# POV_V2.net
KiCad netlist of a schematic drawn in EAGLE
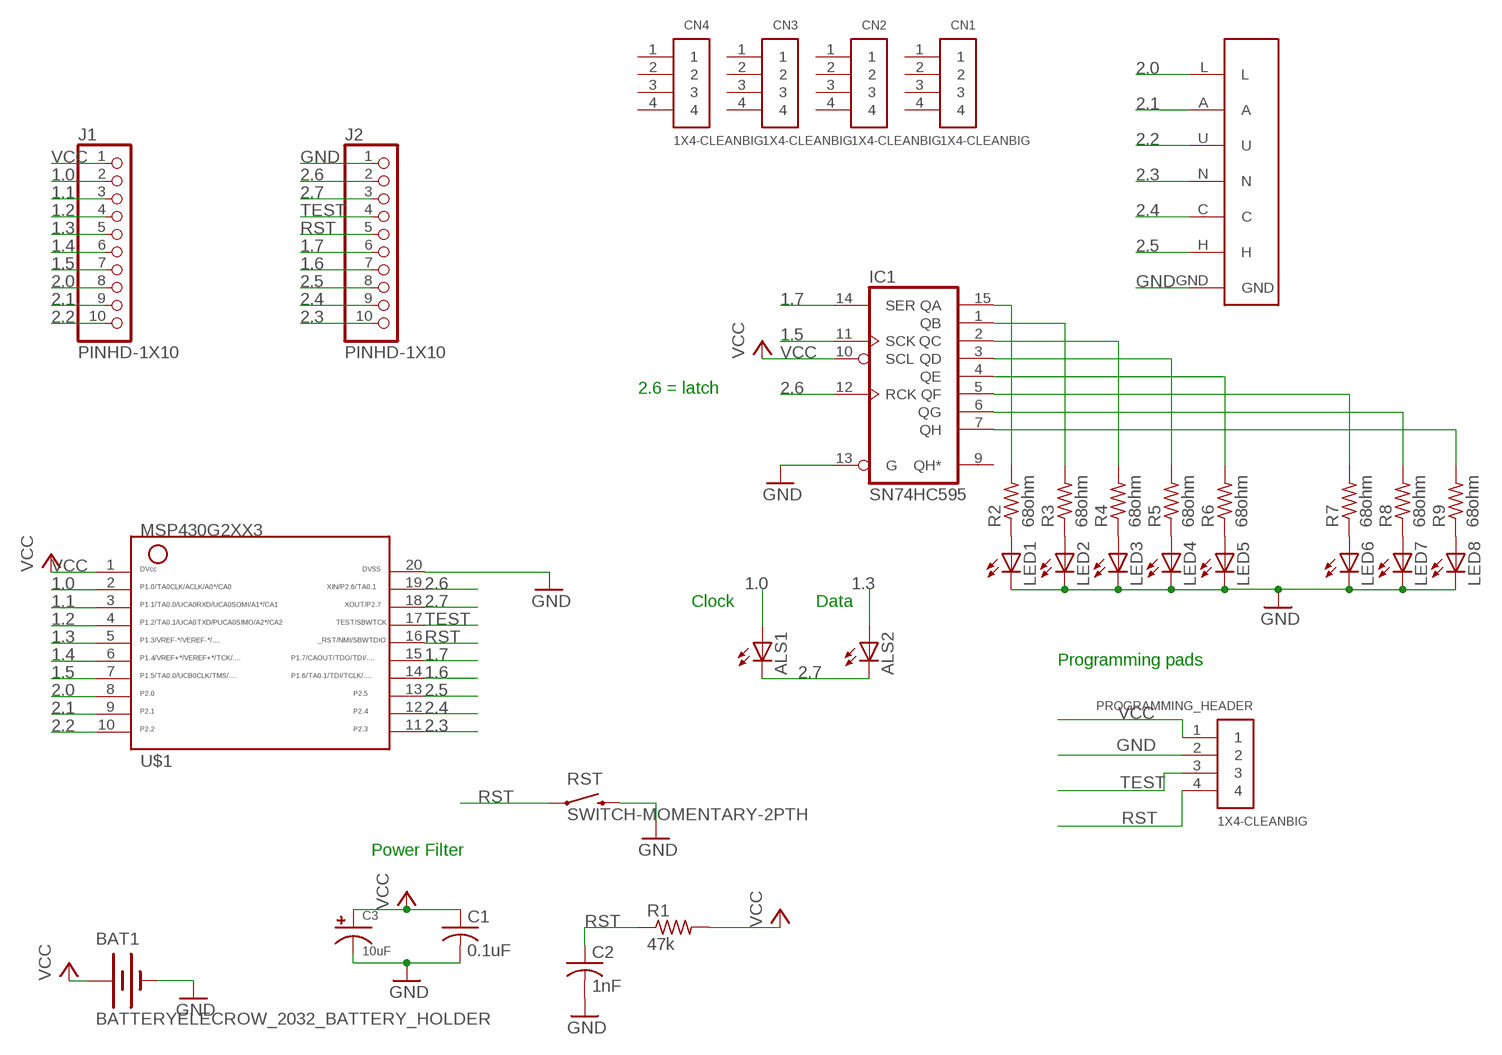
[diagram p0: schematic, sheet 1]

(export (version "E")
  (design (tool "Eeschema 10.0.6"))
  (components
    (comp (ref "ALS1")
      (value "LED3MM")
      (footprint "eagle-import:LED3MM")
      (libsource (lib "eagle-import") (part "LED3MM"))
    )
    (comp (ref "ALS2")
      (value "LED3MM")
      (footprint "eagle-import:LED3MM")
      (libsource (lib "eagle-import") (part "LED3MM"))
    )
    (comp (ref "BAT1")
      (value "BATTERYELECROW_2032_BATTERY_HOLDER")
      (footprint "eagle-import:BATTCON_20MM_4LEGS")
      (libsource (lib "eagle-import") (part "BATTERYELECROW_2032_BATTERY_HOLDER"))
    )
    (comp (ref "C1")
      (value "0.1uF")
      (footprint "eagle-import:C025-024X044")
      (libsource (lib "eagle-import") (part "C-US025-024X044"))
    )
    (comp (ref "C2")
      (value "1nF")
      (footprint "eagle-import:C025-024X044")
      (libsource (lib "eagle-import") (part "C-US025-024X044"))
    )
    (comp (ref "C3")
      (value "10uF")
      (footprint "eagle-import:E2,5-5")
      (libsource (lib "eagle-import") (part "CPOL-US"))
    )
    (comp (ref "CN1")
      (value "1X4-CLEANBIG")
      (footprint "eagle-import:1X04-CLEANBIG")
      (libsource (lib "eagle-import") (part "adafruit_1X4-CLEANBIG"))
    )
    (comp (ref "CN2")
      (value "1X4-CLEANBIG")
      (footprint "eagle-import:1X04-CLEANBIG")
      (libsource (lib "eagle-import") (part "adafruit_1X4-CLEANBIG"))
    )
    (comp (ref "CN3")
      (value "1X4-CLEANBIG")
      (footprint "eagle-import:1X04-CLEANBIG")
      (libsource (lib "eagle-import") (part "adafruit_1X4-CLEANBIG"))
    )
    (comp (ref "CN4")
      (value "1X4-CLEANBIG")
      (footprint "eagle-import:1X04-CLEANBIG")
      (libsource (lib "eagle-import") (part "adafruit_1X4-CLEANBIG"))
    )
    (comp (ref "IC1")
      (value "SN74HC595")
      (footprint "eagle-import:DIL16")
      (libsource (lib "eagle-import") (part "74595NLS"))
    )
    (comp (ref "J1")
      (value "PINHD-1X10")
      (footprint "eagle-import:1X10-BIG")
      (libsource (lib "eagle-import") (part "PINHD-1X10"))
    )
    (comp (ref "J2")
      (value "PINHD-1X10")
      (footprint "eagle-import:1X10-BIG")
      (libsource (lib "eagle-import") (part "PINHD-1X10"))
    )
    (comp (ref "LED1")
      (value "LED3MM")
      (footprint "eagle-import:LED3MM")
      (libsource (lib "eagle-import") (part "LED3MM"))
    )
    (comp (ref "LED2")
      (value "LED3MM")
      (footprint "eagle-import:LED3MM")
      (libsource (lib "eagle-import") (part "LED3MM"))
    )
    (comp (ref "LED3")
      (value "LED3MM")
      (footprint "eagle-import:LED3MM")
      (libsource (lib "eagle-import") (part "LED3MM"))
    )
    (comp (ref "LED4")
      (value "LED3MM")
      (footprint "eagle-import:LED3MM")
      (libsource (lib "eagle-import") (part "LED3MM"))
    )
    (comp (ref "LED5")
      (value "LED3MM")
      (footprint "eagle-import:LED3MM")
      (libsource (lib "eagle-import") (part "LED3MM"))
    )
    (comp (ref "LED6")
      (value "LED3MM")
      (footprint "eagle-import:LED3MM")
      (libsource (lib "eagle-import") (part "LED3MM"))
    )
    (comp (ref "LED7")
      (value "LED3MM")
      (footprint "eagle-import:LED3MM")
      (libsource (lib "eagle-import") (part "LED3MM"))
    )
    (comp (ref "LED8")
      (value "LED3MM")
      (footprint "eagle-import:LED3MM")
      (libsource (lib "eagle-import") (part "LED3MM"))
    )
    (comp (ref "PROGRAMMING_HEADER")
      (value "1X4-CLEANBIG")
      (footprint "eagle-import:1X04-CLEANBIG")
      (libsource (lib "eagle-import") (part "1X4-CLEANBIG"))
    )
    (comp (ref "R1")
      (value "47k")
      (footprint "eagle-import:0204_7")
      (libsource (lib "eagle-import") (part "R-US_0204/7"))
    )
    (comp (ref "R2")
      (value "68ohm")
      (footprint "eagle-import:0204_7")
      (libsource (lib "eagle-import") (part "resistor_R-US_0204/7"))
    )
    (comp (ref "R3")
      (value "68ohm")
      (footprint "eagle-import:0204_7")
      (libsource (lib "eagle-import") (part "resistor_R-US_0204/7"))
    )
    (comp (ref "R4")
      (value "68ohm")
      (footprint "eagle-import:0204_7")
      (libsource (lib "eagle-import") (part "resistor_R-US_0204/7"))
    )
    (comp (ref "R5")
      (value "68ohm")
      (footprint "eagle-import:0204_7")
      (libsource (lib "eagle-import") (part "resistor_R-US_0204/7"))
    )
    (comp (ref "R6")
      (value "68ohm")
      (footprint "eagle-import:0204_7")
      (libsource (lib "eagle-import") (part "resistor_R-US_0204/7"))
    )
    (comp (ref "R7")
      (value "68ohm")
      (footprint "eagle-import:0204_7")
      (libsource (lib "eagle-import") (part "resistor_R-US_0204/7"))
    )
    (comp (ref "R8")
      (value "68ohm")
      (footprint "eagle-import:0204_7")
      (libsource (lib "eagle-import") (part "resistor_R-US_0204/7"))
    )
    (comp (ref "R9")
      (value "68ohm")
      (footprint "eagle-import:0204_7")
      (libsource (lib "eagle-import") (part "resistor_R-US_0204/7"))
    )
    (comp (ref "RST")
      (value "SWITCH-MOMENTARY-2PTH")
      (footprint "eagle-import:TACTILE-PTH")
      (libsource (lib "eagle-import") (part "SWITCH-MOMENTARY-2PTH"))
    )
    (comp (ref "U$1")
      (value "G2553")
      (footprint "eagle-import:N20")
      (libsource (lib "eagle-import") (part "G2XX3---N20"))
    )
    (comp (ref "U$5")
      (value "LAUNCH_SLIDER")
      (footprint "eagle-import:LAUNCHYOURDESIGN_CAPT_SLIDER")
      (libsource (lib "eagle-import") (part "LAUNCH_SLIDER"))
    )
  )
  (nets
    (net (code "1") (name "/1.0") (class "Default")
      (node (ref "ALS1") (pin "A") (pinfunction "A_A") (pintype "passive"))
      (node (ref "J1") (pin "2") (pinfunction "2_2") (pintype "passive"))
      (node (ref "U$1") (pin "2") (pinfunction "2_2") (pintype "bidirectional"))
    )
    (net (code "2") (name "/1.1") (class "Default")
      (node (ref "J1") (pin "3") (pinfunction "3_3") (pintype "passive"))
      (node (ref "U$1") (pin "3") (pinfunction "3_3") (pintype "bidirectional"))
    )
    (net (code "3") (name "/1.2") (class "Default")
      (node (ref "J1") (pin "4") (pinfunction "4_4") (pintype "passive"))
      (node (ref "U$1") (pin "4") (pinfunction "4_4") (pintype "bidirectional"))
    )
    (net (code "4") (name "/1.3") (class "Default")
      (node (ref "ALS2") (pin "A") (pinfunction "A_A") (pintype "passive"))
      (node (ref "J1") (pin "5") (pinfunction "5_5") (pintype "passive"))
      (node (ref "U$1") (pin "5") (pinfunction "5_5") (pintype "bidirectional"))
    )
    (net (code "5") (name "/1.4") (class "Default")
      (node (ref "J1") (pin "6") (pinfunction "6_6") (pintype "passive"))
      (node (ref "U$1") (pin "6") (pinfunction "6_6") (pintype "bidirectional"))
    )
    (net (code "6") (name "/1.5") (class "Default")
      (node (ref "IC1") (pin "11") (pinfunction "SCK_11") (pintype "input"))
      (node (ref "J1") (pin "7") (pinfunction "7_7") (pintype "passive"))
      (node (ref "U$1") (pin "7") (pinfunction "7_7") (pintype "bidirectional"))
    )
    (net (code "7") (name "/1.6") (class "Default")
      (node (ref "J2") (pin "7") (pinfunction "7_7") (pintype "passive"))
      (node (ref "U$1") (pin "14") (pinfunction "14_14") (pintype "bidirectional"))
    )
    (net (code "8") (name "/1.7") (class "Default")
      (node (ref "IC1") (pin "14") (pinfunction "SER_14") (pintype "input"))
      (node (ref "J2") (pin "6") (pinfunction "6_6") (pintype "passive"))
      (node (ref "U$1") (pin "15") (pinfunction "15_15") (pintype "bidirectional"))
    )
    (net (code "9") (name "/2.0") (class "Default")
      (node (ref "J1") (pin "8") (pinfunction "8_8") (pintype "passive"))
      (node (ref "U$1") (pin "8") (pinfunction "8_8") (pintype "bidirectional"))
      (node (ref "U$5") (pin "L") (pinfunction "L_L") (pintype "bidirectional"))
    )
    (net (code "10") (name "/2.1") (class "Default")
      (node (ref "J1") (pin "9") (pinfunction "9_9") (pintype "passive"))
      (node (ref "U$1") (pin "9") (pinfunction "9_9") (pintype "bidirectional"))
      (node (ref "U$5") (pin "A") (pinfunction "A_A") (pintype "bidirectional"))
    )
    (net (code "11") (name "/2.2") (class "Default")
      (node (ref "J1") (pin "10") (pinfunction "10_10") (pintype "passive"))
      (node (ref "U$1") (pin "10") (pinfunction "10_10") (pintype "bidirectional"))
      (node (ref "U$5") (pin "U") (pinfunction "U_U") (pintype "bidirectional"))
    )
    (net (code "12") (name "/2.3") (class "Default")
      (node (ref "J2") (pin "10") (pinfunction "10_10") (pintype "passive"))
      (node (ref "U$1") (pin "11") (pinfunction "11_11") (pintype "bidirectional"))
      (node (ref "U$5") (pin "N") (pinfunction "N_N") (pintype "bidirectional"))
    )
    (net (code "13") (name "/2.4") (class "Default")
      (node (ref "J2") (pin "9") (pinfunction "9_9") (pintype "passive"))
      (node (ref "U$1") (pin "12") (pinfunction "12_12") (pintype "bidirectional"))
      (node (ref "U$5") (pin "C") (pinfunction "C_C") (pintype "bidirectional"))
    )
    (net (code "14") (name "/2.5") (class "Default")
      (node (ref "J2") (pin "8") (pinfunction "8_8") (pintype "passive"))
      (node (ref "U$1") (pin "13") (pinfunction "13_13") (pintype "bidirectional"))
      (node (ref "U$5") (pin "H") (pinfunction "H_H") (pintype "bidirectional"))
    )
    (net (code "15") (name "/2.6") (class "Default")
      (node (ref "IC1") (pin "12") (pinfunction "RCK_12") (pintype "input"))
      (node (ref "J2") (pin "2") (pinfunction "2_2") (pintype "passive"))
      (node (ref "U$1") (pin "19") (pinfunction "19_19") (pintype "bidirectional"))
    )
    (net (code "16") (name "/2.7") (class "Default")
      (node (ref "ALS1") (pin "K") (pinfunction "C_K") (pintype "passive"))
      (node (ref "ALS2") (pin "K") (pinfunction "C_K") (pintype "passive"))
      (node (ref "J2") (pin "3") (pinfunction "3_3") (pintype "passive"))
      (node (ref "U$1") (pin "18") (pinfunction "18_18") (pintype "bidirectional"))
    )
    (net (code "17") (name "/RST") (class "Default")
      (node (ref "C2") (pin "1") (pinfunction "1_1") (pintype "passive"))
      (node (ref "J2") (pin "5") (pinfunction "5_5") (pintype "passive"))
      (node (ref "PROGRAMMING_HEADER") (pin "4") (pinfunction "4_4") (pintype "bidirectional"))
      (node (ref "R1") (pin "1") (pinfunction "1_1") (pintype "passive"))
      (node (ref "RST") (pin "1") (pinfunction "1_1") (pintype "passive"))
      (node (ref "RST") (pin "2") (pinfunction "1_2") (pintype "passive"))
      (node (ref "U$1") (pin "16") (pinfunction "16_16") (pintype "bidirectional"))
    )
    (net (code "18") (name "/TEST") (class "Default")
      (node (ref "J2") (pin "4") (pinfunction "4_4") (pintype "passive"))
      (node (ref "PROGRAMMING_HEADER") (pin "3") (pinfunction "3_3") (pintype "bidirectional"))
      (node (ref "U$1") (pin "17") (pinfunction "17_17") (pintype "bidirectional"))
    )
    (net (code "19") (name "GND") (class "Default")
      (node (ref "BAT1") (pin "GND") (pinfunction "-_GND") (pintype "power_in"))
      (node (ref "C1") (pin "2") (pinfunction "2_2") (pintype "passive"))
      (node (ref "C2") (pin "2") (pinfunction "2_2") (pintype "passive"))
      (node (ref "C3") (pin "-") (pinfunction "-_-") (pintype "bidirectional"))
      (node (ref "IC1") (pin "13") (pinfunction "G_13") (pintype "input"))
      (node (ref "J2") (pin "1") (pinfunction "1_1") (pintype "passive"))
      (node (ref "LED1") (pin "K") (pinfunction "C_K") (pintype "passive"))
      (node (ref "LED2") (pin "K") (pinfunction "C_K") (pintype "passive"))
      (node (ref "LED3") (pin "K") (pinfunction "C_K") (pintype "passive"))
      (node (ref "LED4") (pin "K") (pinfunction "C_K") (pintype "passive"))
      (node (ref "LED5") (pin "K") (pinfunction "C_K") (pintype "passive"))
      (node (ref "LED6") (pin "K") (pinfunction "C_K") (pintype "passive"))
      (node (ref "LED7") (pin "K") (pinfunction "C_K") (pintype "passive"))
      (node (ref "LED8") (pin "K") (pinfunction "C_K") (pintype "passive"))
      (node (ref "PROGRAMMING_HEADER") (pin "2") (pinfunction "2_2") (pintype "bidirectional"))
      (node (ref "RST") (pin "3") (pinfunction "2_3") (pintype "passive"))
      (node (ref "RST") (pin "4") (pinfunction "2_4") (pintype "passive"))
      (node (ref "U$1") (pin "20") (pinfunction "20_20") (pintype "bidirectional"))
      (node (ref "U$5") (pin "GND") (pinfunction "GND_GND") (pintype "bidirectional"))
    )
    (net (code "20") (name "Net-(IC1A-QA)") (class "Default")
      (node (ref "IC1") (pin "15") (pinfunction "QA_15") (pintype "tri_state"))
      (node (ref "R2") (pin "2") (pinfunction "2_2") (pintype "passive"))
    )
    (net (code "21") (name "Net-(IC1A-QB)") (class "Default")
      (node (ref "IC1") (pin "1") (pinfunction "QB_1") (pintype "tri_state"))
      (node (ref "R3") (pin "2") (pinfunction "2_2") (pintype "passive"))
    )
    (net (code "22") (name "Net-(IC1A-QC)") (class "Default")
      (node (ref "IC1") (pin "2") (pinfunction "QC_2") (pintype "tri_state"))
      (node (ref "R4") (pin "2") (pinfunction "2_2") (pintype "passive"))
    )
    (net (code "23") (name "Net-(IC1A-QD)") (class "Default")
      (node (ref "IC1") (pin "3") (pinfunction "QD_3") (pintype "tri_state"))
      (node (ref "R5") (pin "2") (pinfunction "2_2") (pintype "passive"))
    )
    (net (code "24") (name "Net-(IC1A-QE)") (class "Default")
      (node (ref "IC1") (pin "4") (pinfunction "QE_4") (pintype "tri_state"))
      (node (ref "R6") (pin "2") (pinfunction "2_2") (pintype "passive"))
    )
    (net (code "25") (name "Net-(IC1A-QF)") (class "Default")
      (node (ref "IC1") (pin "5") (pinfunction "QF_5") (pintype "tri_state"))
      (node (ref "R7") (pin "2") (pinfunction "2_2") (pintype "passive"))
    )
    (net (code "26") (name "Net-(IC1A-QG)") (class "Default")
      (node (ref "IC1") (pin "6") (pinfunction "QG_6") (pintype "tri_state"))
      (node (ref "R8") (pin "2") (pinfunction "2_2") (pintype "passive"))
    )
    (net (code "27") (name "Net-(IC1A-QH)") (class "Default")
      (node (ref "IC1") (pin "7") (pinfunction "QH_7") (pintype "tri_state"))
      (node (ref "R9") (pin "2") (pinfunction "2_2") (pintype "passive"))
    )
    (net (code "28") (name "Net-(LED1-PadA)") (class "Default")
      (node (ref "LED1") (pin "A") (pinfunction "A_A") (pintype "passive"))
      (node (ref "R2") (pin "1") (pinfunction "1_1") (pintype "passive"))
    )
    (net (code "29") (name "Net-(LED2-PadA)") (class "Default")
      (node (ref "LED2") (pin "A") (pinfunction "A_A") (pintype "passive"))
      (node (ref "R3") (pin "1") (pinfunction "1_1") (pintype "passive"))
    )
    (net (code "30") (name "Net-(LED3-PadA)") (class "Default")
      (node (ref "LED3") (pin "A") (pinfunction "A_A") (pintype "passive"))
      (node (ref "R4") (pin "1") (pinfunction "1_1") (pintype "passive"))
    )
    (net (code "31") (name "Net-(LED4-PadA)") (class "Default")
      (node (ref "LED4") (pin "A") (pinfunction "A_A") (pintype "passive"))
      (node (ref "R5") (pin "1") (pinfunction "1_1") (pintype "passive"))
    )
    (net (code "32") (name "Net-(LED5-PadA)") (class "Default")
      (node (ref "LED5") (pin "A") (pinfunction "A_A") (pintype "passive"))
      (node (ref "R6") (pin "1") (pinfunction "1_1") (pintype "passive"))
    )
    (net (code "33") (name "Net-(LED6-PadA)") (class "Default")
      (node (ref "LED6") (pin "A") (pinfunction "A_A") (pintype "passive"))
      (node (ref "R7") (pin "1") (pinfunction "1_1") (pintype "passive"))
    )
    (net (code "34") (name "Net-(LED7-PadA)") (class "Default")
      (node (ref "LED7") (pin "A") (pinfunction "A_A") (pintype "passive"))
      (node (ref "R8") (pin "1") (pinfunction "1_1") (pintype "passive"))
    )
    (net (code "35") (name "Net-(LED8-PadA)") (class "Default")
      (node (ref "LED8") (pin "A") (pinfunction "A_A") (pintype "passive"))
      (node (ref "R9") (pin "1") (pinfunction "1_1") (pintype "passive"))
    )
    (net (code "36") (name "VCC") (class "Default")
      (node (ref "BAT1") (pin "VCC1") (pinfunction "+_VCC1") (pintype "power_in"))
      (node (ref "BAT1") (pin "VCC2") (pinfunction "+_VCC2") (pintype "power_in"))
      (node (ref "BAT1") (pin "VCC3") (pinfunction "+_VCC3") (pintype "power_in"))
      (node (ref "C1") (pin "1") (pinfunction "1_1") (pintype "passive"))
      (node (ref "C3") (pin "+") (pinfunction "+_+") (pintype "bidirectional"))
      (node (ref "IC1") (pin "10") (pinfunction "SCL_10") (pintype "input"))
      (node (ref "J1") (pin "1") (pinfunction "1_1") (pintype "passive"))
      (node (ref "PROGRAMMING_HEADER") (pin "1") (pinfunction "1_1") (pintype "bidirectional"))
      (node (ref "R1") (pin "2") (pinfunction "2_2") (pintype "passive"))
      (node (ref "U$1") (pin "1") (pinfunction "1_1") (pintype "bidirectional"))
    )
    (net (code "37") (name "unconnected-(CN1-Pad1)") (class "Default")
      (node (ref "CN1") (pin "1") (pinfunction "1_1") (pintype "bidirectional"))
    )
    (net (code "38") (name "unconnected-(CN1-Pad2)") (class "Default")
      (node (ref "CN1") (pin "2") (pinfunction "2_2") (pintype "bidirectional"))
    )
    (net (code "39") (name "unconnected-(CN1-Pad3)") (class "Default")
      (node (ref "CN1") (pin "3") (pinfunction "3_3") (pintype "bidirectional"))
    )
    (net (code "40") (name "unconnected-(CN1-Pad4)") (class "Default")
      (node (ref "CN1") (pin "4") (pinfunction "4_4") (pintype "bidirectional"))
    )
    (net (code "41") (name "unconnected-(CN2-Pad1)") (class "Default")
      (node (ref "CN2") (pin "1") (pinfunction "1_1") (pintype "bidirectional"))
    )
    (net (code "42") (name "unconnected-(CN2-Pad2)") (class "Default")
      (node (ref "CN2") (pin "2") (pinfunction "2_2") (pintype "bidirectional"))
    )
    (net (code "43") (name "unconnected-(CN2-Pad3)") (class "Default")
      (node (ref "CN2") (pin "3") (pinfunction "3_3") (pintype "bidirectional"))
    )
    (net (code "44") (name "unconnected-(CN2-Pad4)") (class "Default")
      (node (ref "CN2") (pin "4") (pinfunction "4_4") (pintype "bidirectional"))
    )
    (net (code "45") (name "unconnected-(CN3-Pad1)") (class "Default")
      (node (ref "CN3") (pin "1") (pinfunction "1_1") (pintype "bidirectional"))
    )
    (net (code "46") (name "unconnected-(CN3-Pad2)") (class "Default")
      (node (ref "CN3") (pin "2") (pinfunction "2_2") (pintype "bidirectional"))
    )
    (net (code "47") (name "unconnected-(CN3-Pad3)") (class "Default")
      (node (ref "CN3") (pin "3") (pinfunction "3_3") (pintype "bidirectional"))
    )
    (net (code "48") (name "unconnected-(CN3-Pad4)") (class "Default")
      (node (ref "CN3") (pin "4") (pinfunction "4_4") (pintype "bidirectional"))
    )
    (net (code "49") (name "unconnected-(CN4-Pad1)") (class "Default")
      (node (ref "CN4") (pin "1") (pinfunction "1_1") (pintype "bidirectional"))
    )
    (net (code "50") (name "unconnected-(CN4-Pad2)") (class "Default")
      (node (ref "CN4") (pin "2") (pinfunction "2_2") (pintype "bidirectional"))
    )
    (net (code "51") (name "unconnected-(CN4-Pad3)") (class "Default")
      (node (ref "CN4") (pin "3") (pinfunction "3_3") (pintype "bidirectional"))
    )
    (net (code "52") (name "unconnected-(CN4-Pad4)") (class "Default")
      (node (ref "CN4") (pin "4") (pinfunction "4_4") (pintype "bidirectional"))
    )
    (net (code "53") (name "unconnected-(IC1A-QH*-Pad9)") (class "Default")
      (node (ref "IC1") (pin "9") (pinfunction "QH*_9") (pintype "tri_state"))
    )
  )
)
